# floppy.net
KiCad netlist of a schematic drawn in EAGLE
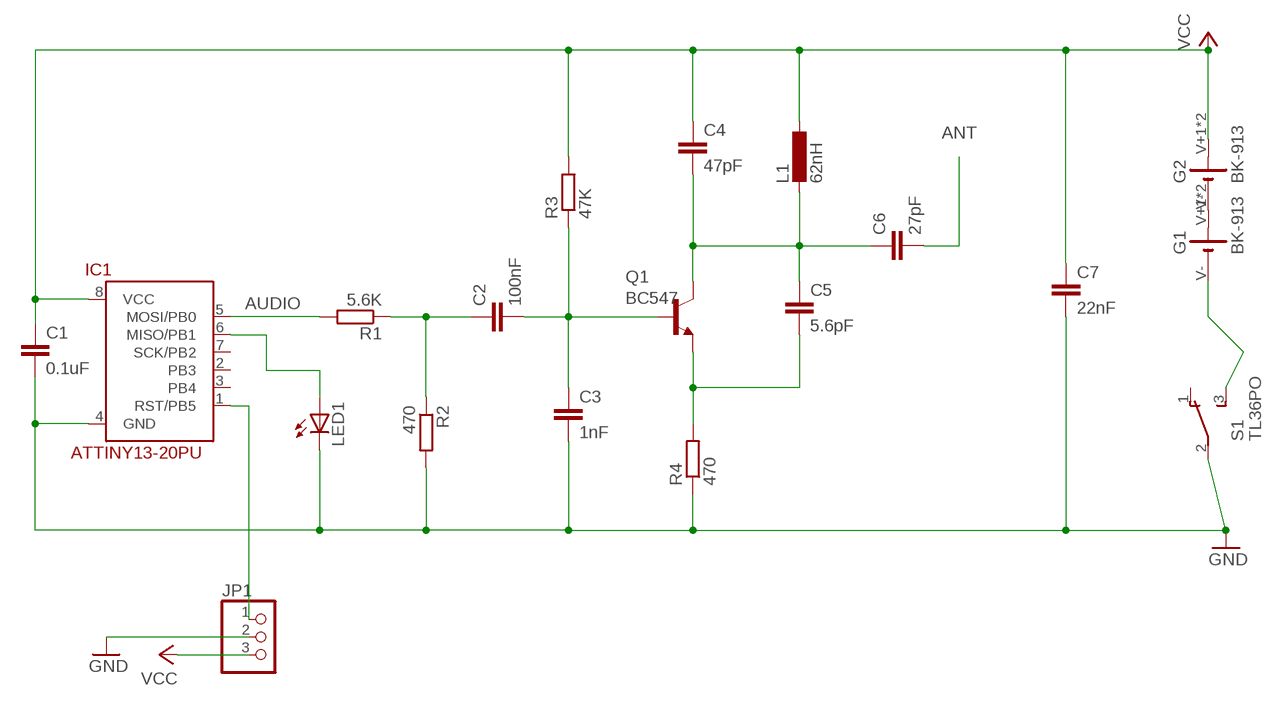
[diagram p0: schematic, sheet 1]

(export (version "E")
  (design (tool "Eeschema 10.0.6"))
  (components
    (comp (ref "C1")
      (value "0.1uF")
      (footprint "eagle-import:C025-025X050")
      (libsource (lib "eagle-import") (part "C-EU025-025X050"))
    )
    (comp (ref "C2")
      (value "100nF")
      (footprint "eagle-import:C025-025X050")
      (libsource (lib "eagle-import") (part "C-EU025-025X050"))
    )
    (comp (ref "C3")
      (value "1nF")
      (footprint "eagle-import:C025-025X050")
      (libsource (lib "eagle-import") (part "C-EU025-025X050"))
    )
    (comp (ref "C4")
      (value "47pF")
      (footprint "eagle-import:C025-025X050")
      (libsource (lib "eagle-import") (part "C-EU025-025X050"))
    )
    (comp (ref "C5")
      (value "5.6pF")
      (footprint "eagle-import:C025-025X050")
      (libsource (lib "eagle-import") (part "C-EU025-025X050"))
    )
    (comp (ref "C6")
      (value "27pF")
      (footprint "eagle-import:C025-025X050")
      (libsource (lib "eagle-import") (part "C-EU025-025X050"))
    )
    (comp (ref "C7")
      (value "22nF")
      (footprint "eagle-import:C025-025X050")
      (libsource (lib "eagle-import") (part "C-EU025-025X050"))
    )
    (comp (ref "G1")
      (value "BK-913")
      (footprint "eagle-import:BK-913")
      (libsource (lib "eagle-import") (part "BK-913"))
    )
    (comp (ref "G2")
      (value "BK-913")
      (footprint "eagle-import:BK-913")
      (libsource (lib "eagle-import") (part "BK-913"))
    )
    (comp (ref "IC1")
      (value "ATTINY13-20PU")
      (footprint "eagle-import:DIL08")
      (libsource (lib "eagle-import") (part "ATTINY13-20PU"))
    )
    (comp (ref "JP1")
      (value "PINHD-1X3")
      (footprint "eagle-import:1X03")
      (libsource (lib "eagle-import") (part "PINHD-1X3"))
    )
    (comp (ref "L1")
      (value "62nH")
      (footprint "eagle-import:0207_7")
      (libsource (lib "eagle-import") (part "L-EU0207/7"))
    )
    (comp (ref "LED1")
      (value "LED5MM")
      (footprint "eagle-import:LED5MM")
      (libsource (lib "eagle-import") (part "LED5MM"))
    )
    (comp (ref "Q1")
      (value "BC547")
      (footprint "eagle-import:TO92")
      (libsource (lib "eagle-import") (part "BC547"))
    )
    (comp (ref "R1")
      (value "5.6K")
      (footprint "eagle-import:0207_7")
      (libsource (lib "eagle-import") (part "R-EU_0207/7"))
    )
    (comp (ref "R2")
      (value "470")
      (footprint "eagle-import:0207_7")
      (libsource (lib "eagle-import") (part "R-EU_0207/7"))
    )
    (comp (ref "R3")
      (value "47K")
      (footprint "eagle-import:0207_7")
      (libsource (lib "eagle-import") (part "R-EU_0207/7"))
    )
    (comp (ref "R4")
      (value "470")
      (footprint "eagle-import:0207_7")
      (libsource (lib "eagle-import") (part "R-EU_0207/7"))
    )
    (comp (ref "S1")
      (value "TL36PO")
      (footprint "eagle-import:TL3XPO")
      (libsource (lib "eagle-import") (part "TL36PO"))
    )
  )
  (nets
    (net (code "1") (name "/ANT") (class "Default")
      (node (ref "C6") (pin "2") (pinfunction "2_2") (pintype "passive"))
    )
    (net (code "2") (name "/AUDIO") (class "Default")
      (node (ref "C2") (pin "1") (pinfunction "1_1") (pintype "passive"))
      (node (ref "R1") (pin "1") (pinfunction "1_1") (pintype "passive"))
      (node (ref "R2") (pin "1") (pinfunction "1_1") (pintype "passive"))
    )
    (net (code "3") (name "GND") (class "Default")
      (node (ref "C1") (pin "2") (pinfunction "2_2") (pintype "passive"))
      (node (ref "C3") (pin "2") (pinfunction "2_2") (pintype "passive"))
      (node (ref "C7") (pin "2") (pinfunction "2_2") (pintype "passive"))
      (node (ref "IC1") (pin "4") (pinfunction "GND_4") (pintype "power_in"))
      (node (ref "JP1") (pin "2") (pinfunction "2_2") (pintype "passive"))
      (node (ref "LED1") (pin "K") (pinfunction "C_K") (pintype "passive"))
      (node (ref "R2") (pin "2") (pinfunction "2_2") (pintype "passive"))
      (node (ref "R4") (pin "1") (pinfunction "1_1") (pintype "passive"))
      (node (ref "S1") (pin "2") (pinfunction "P_2") (pintype "passive"))
    )
    (net (code "4") (name "Net-(G1-V+-PadV+1)") (class "Default")
      (node (ref "G1") (pin "V+1") (pinfunction "V+_V+1") (pintype "passive"))
      (node (ref "G1") (pin "V+2") (pinfunction "V+_V+2") (pintype "passive"))
      (node (ref "G2") (pin "V-") (pinfunction "V-_V-") (pintype "passive"))
    )
    (net (code "5") (name "Net-(IC1-MISO{slash}PB1)") (class "Default")
      (node (ref "IC1") (pin "6") (pinfunction "MISO/PB1_6") (pintype "bidirectional"))
      (node (ref "LED1") (pin "A") (pinfunction "A_A") (pintype "passive"))
    )
    (net (code "6") (name "Net-(IC1-MOSI{slash}PB0)") (class "Default")
      (node (ref "IC1") (pin "5") (pinfunction "MOSI/PB0_5") (pintype "bidirectional"))
      (node (ref "R1") (pin "2") (pinfunction "2_2") (pintype "passive"))
    )
    (net (code "7") (name "Net-(IC1-RST{slash}PB5)") (class "Default")
      (node (ref "IC1") (pin "1") (pinfunction "RST/PB5_1") (pintype "bidirectional"))
      (node (ref "JP1") (pin "1") (pinfunction "1_1") (pintype "passive"))
    )
    (net (code "8") (name "Net-(Q1-B)") (class "Default")
      (node (ref "C2") (pin "2") (pinfunction "2_2") (pintype "passive"))
      (node (ref "C3") (pin "1") (pinfunction "1_1") (pintype "passive"))
      (node (ref "Q1") (pin "2") (pinfunction "B_2") (pintype "passive"))
      (node (ref "R3") (pin "1") (pinfunction "1_1") (pintype "passive"))
    )
    (net (code "9") (name "Net-(Q1-C)") (class "Default")
      (node (ref "C4") (pin "2") (pinfunction "2_2") (pintype "passive"))
      (node (ref "C5") (pin "1") (pinfunction "1_1") (pintype "passive"))
      (node (ref "C6") (pin "1") (pinfunction "1_1") (pintype "passive"))
      (node (ref "L1") (pin "2") (pinfunction "2_2") (pintype "passive"))
      (node (ref "Q1") (pin "3") (pinfunction "C_3") (pintype "passive"))
    )
    (net (code "10") (name "Net-(Q1-E)") (class "Default")
      (node (ref "C5") (pin "2") (pinfunction "2_2") (pintype "passive"))
      (node (ref "Q1") (pin "1") (pinfunction "E_1") (pintype "passive"))
      (node (ref "R4") (pin "2") (pinfunction "2_2") (pintype "passive"))
    )
    (net (code "11") (name "Net-(S1-S)") (class "Default")
      (node (ref "G1") (pin "V-") (pinfunction "V-_V-") (pintype "passive"))
      (node (ref "S1") (pin "3") (pinfunction "S_3") (pintype "passive"))
    )
    (net (code "12") (name "VCC") (class "Default")
      (node (ref "C1") (pin "1") (pinfunction "1_1") (pintype "passive"))
      (node (ref "C4") (pin "1") (pinfunction "1_1") (pintype "passive"))
      (node (ref "C7") (pin "1") (pinfunction "1_1") (pintype "passive"))
      (node (ref "G2") (pin "V+1") (pinfunction "V+_V+1") (pintype "passive"))
      (node (ref "G2") (pin "V+2") (pinfunction "V+_V+2") (pintype "passive"))
      (node (ref "IC1") (pin "8") (pinfunction "VCC_8") (pintype "power_in"))
      (node (ref "JP1") (pin "3") (pinfunction "3_3") (pintype "passive"))
      (node (ref "L1") (pin "1") (pinfunction "1_1") (pintype "passive"))
      (node (ref "R3") (pin "2") (pinfunction "2_2") (pintype "passive"))
    )
    (net (code "13") (name "unconnected-(IC1-PB3-Pad2)") (class "Default")
      (node (ref "IC1") (pin "2") (pinfunction "PB3_2") (pintype "bidirectional"))
    )
    (net (code "14") (name "unconnected-(IC1-PB4-Pad3)") (class "Default")
      (node (ref "IC1") (pin "3") (pinfunction "PB4_3") (pintype "bidirectional"))
    )
    (net (code "15") (name "unconnected-(IC1-SCK{slash}PB2-Pad7)") (class "Default")
      (node (ref "IC1") (pin "7") (pinfunction "SCK/PB2_7") (pintype "bidirectional"))
    )
    (net (code "16") (name "unconnected-(S1-O-Pad1)") (class "Default")
      (node (ref "S1") (pin "1") (pinfunction "O_1") (pintype "passive"))
    )
  )
)
